# OpenMPPT2-Control.net
KiCad netlist of a schematic drawn in Altium Designer
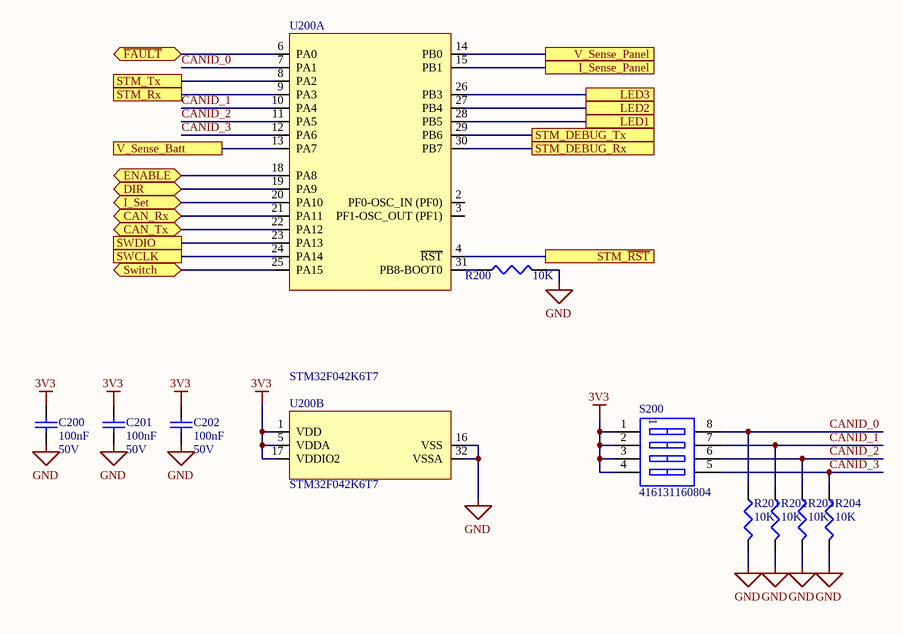
[diagram p0: OpenMPPT2-Control.SchDoc]

(export (version "E")
  (design (tool "Eeschema 10.0.6"))
  (components
    (comp (ref "C200")
      (value "100nF")
      (footprint "C0603")
      (description "Capacitor, 100nF, 50V, X7R")
      (fields (field (name "VOLTAGE RATING") "50V"))
      (libsource (lib "SBT_Capacitors_Ceramic") (part "100nF/0603/CER/50V"))
    )
    (comp (ref "C201")
      (value "100nF")
      (footprint "C0603")
      (description "Capacitor, 100nF, 50V, X7R")
      (fields (field (name "VOLTAGE RATING") "50V"))
      (libsource (lib "SBT_Capacitors_Ceramic") (part "100nF/0603/CER/50V"))
    )
    (comp (ref "C202")
      (value "100nF")
      (footprint "C0603")
      (description "Capacitor, 100nF, 50V, X7R")
      (fields (field (name "VOLTAGE RATING") "50V"))
      (libsource (lib "SBT_Capacitors_Ceramic") (part "100nF/0603/CER/50V"))
    )
    (comp (ref "R200")
      (value "10K")
      (footprint "0603")
      (description "Resistor, 10K, 1%, 0.063W, 50V, 100PPM, 0603")
      (libsource (lib "SBT_Resistors_SMD") (part "10K/0603/0063W/50V"))
    )
    (comp (ref "R201")
      (value "10K")
      (footprint "0603")
      (description "Resistor, 10K, 1%, 0.063W, 50V, 100PPM, 0603")
      (libsource (lib "SBT_Resistors_SMD") (part "10K/0603/0063W/50V"))
    )
    (comp (ref "R202")
      (value "10K")
      (footprint "0603")
      (description "Resistor, 10K, 1%, 0.063W, 50V, 100PPM, 0603")
      (libsource (lib "SBT_Resistors_SMD") (part "10K/0603/0063W/50V"))
    )
    (comp (ref "R203")
      (value "10K")
      (footprint "0603")
      (description "Resistor, 10K, 1%, 0.063W, 50V, 100PPM, 0603")
      (libsource (lib "SBT_Resistors_SMD") (part "10K/0603/0063W/50V"))
    )
    (comp (ref "R204")
      (value "10K")
      (footprint "0603")
      (description "Resistor, 10K, 1%, 0.063W, 50V, 100PPM, 0603")
      (libsource (lib "SBT_Resistors_SMD") (part "10K/0603/0063W/50V"))
    )
    (comp (ref "S200")
      (value "416131160804")
      (footprint "416131160804")
      (description "1.27 mm small compact SMD flat actuator with top tape WS-DISV")
      (fields (field (name "PUBLISHER") "Wurth Elektronik"))
      (libsource (lib "ALTIUM-WS-DISV-rev17b") (part "416131160804"))
    )
    (comp (ref "U200")
      (value "STM32F042K6T7")
      (footprint "LQFP32")
      (description "32 Bit Microcontroller, USB Line, ARM Cortex-M0, 48 MHz, 128 KB, 16 KB, 48, LQFP")
      (libsource (lib "SBT_Microcontrollers") (part "STM32F042K6T7"))
    )
  )
  (nets
    (net (code "1") (name "/CANID_0") (class "Default")
      (node (ref "R201") (pin "1") (pinfunction "1_1") (pintype "passive"))
      (node (ref "S200") (pin "8") (pinfunction "8_8") (pintype "passive"))
      (node (ref "U200") (pin "7") (pinfunction "PA1_7") (pintype "bidirectional"))
    )
    (net (code "2") (name "/CANID_1") (class "Default")
      (node (ref "R202") (pin "1") (pinfunction "1_1") (pintype "passive"))
      (node (ref "S200") (pin "7") (pinfunction "7_7") (pintype "passive"))
      (node (ref "U200") (pin "10") (pinfunction "PA4_10") (pintype "bidirectional"))
    )
    (net (code "3") (name "/CANID_2") (class "Default")
      (node (ref "R203") (pin "1") (pinfunction "1_1") (pintype "passive"))
      (node (ref "S200") (pin "6") (pinfunction "6_6") (pintype "passive"))
      (node (ref "U200") (pin "11") (pinfunction "PA5_11") (pintype "bidirectional"))
    )
    (net (code "4") (name "/CANID_3") (class "Default")
      (node (ref "R204") (pin "1") (pinfunction "1_1") (pintype "passive"))
      (node (ref "S200") (pin "5") (pinfunction "5_5") (pintype "passive"))
      (node (ref "U200") (pin "12") (pinfunction "PA6_12") (pintype "bidirectional"))
    )
    (net (code "5") (name "/CAN_Rx") (class "Default")
      (node (ref "U200") (pin "21") (pinfunction "PA11_21") (pintype "bidirectional"))
    )
    (net (code "6") (name "/CAN_Tx") (class "Default")
      (node (ref "U200") (pin "22") (pinfunction "PA12_22") (pintype "bidirectional"))
    )
    (net (code "7") (name "/DIR") (class "Default")
      (node (ref "U200") (pin "19") (pinfunction "PA9_19") (pintype "bidirectional"))
    )
    (net (code "8") (name "/ENABLE") (class "Default")
      (node (ref "U200") (pin "18") (pinfunction "PA8_18") (pintype "bidirectional"))
    )
    (net (code "9") (name "/I_Sense_Panel") (class "Default")
      (node (ref "U200") (pin "15") (pinfunction "PB1_15") (pintype "bidirectional"))
    )
    (net (code "10") (name "/I_Set") (class "Default")
      (node (ref "U200") (pin "20") (pinfunction "PA10_20") (pintype "bidirectional"))
    )
    (net (code "11") (name "/LED1") (class "Default")
      (node (ref "U200") (pin "28") (pinfunction "PB5_28") (pintype "bidirectional"))
    )
    (net (code "12") (name "/LED2") (class "Default")
      (node (ref "U200") (pin "27") (pinfunction "PB4_27") (pintype "bidirectional"))
    )
    (net (code "13") (name "/LED3") (class "Default")
      (node (ref "U200") (pin "26") (pinfunction "PB3_26") (pintype "bidirectional"))
    )
    (net (code "14") (name "/STM_DEBUG_Rx") (class "Default")
      (node (ref "U200") (pin "30") (pinfunction "PB7_30") (pintype "bidirectional"))
    )
    (net (code "15") (name "/STM_DEBUG_Tx") (class "Default")
      (node (ref "U200") (pin "29") (pinfunction "PB6_29") (pintype "bidirectional"))
    )
    (net (code "16") (name "/STM_Rx") (class "Default")
      (node (ref "U200") (pin "9") (pinfunction "PA3_9") (pintype "bidirectional"))
    )
    (net (code "17") (name "/STM_Tx") (class "Default")
      (node (ref "U200") (pin "8") (pinfunction "PA2_8") (pintype "bidirectional"))
    )
    (net (code "18") (name "/STM_~{RST}") (class "Default")
      (node (ref "U200") (pin "4") (pinfunction "~{RST}_4") (pintype "bidirectional"))
    )
    (net (code "19") (name "/SWCLK") (class "Default")
      (node (ref "U200") (pin "24") (pinfunction "PA14_24") (pintype "bidirectional"))
    )
    (net (code "20") (name "/SWDIO") (class "Default")
      (node (ref "U200") (pin "23") (pinfunction "PA13_23") (pintype "bidirectional"))
    )
    (net (code "21") (name "/Switch") (class "Default")
      (node (ref "U200") (pin "25") (pinfunction "PA15_25") (pintype "bidirectional"))
    )
    (net (code "22") (name "/V_Sense_Batt") (class "Default")
      (node (ref "U200") (pin "13") (pinfunction "PA7_13") (pintype "bidirectional"))
    )
    (net (code "23") (name "/V_Sense_Panel") (class "Default")
      (node (ref "U200") (pin "14") (pinfunction "PB0_14") (pintype "bidirectional"))
    )
    (net (code "24") (name "/~{FAULT}") (class "Default")
      (node (ref "U200") (pin "6") (pinfunction "PA0_6") (pintype "bidirectional"))
    )
    (net (code "25") (name "3V3") (class "Default")
      (node (ref "C200") (pin "2") (pinfunction "2_2") (pintype "passive"))
      (node (ref "C201") (pin "2") (pinfunction "2_2") (pintype "passive"))
      (node (ref "C202") (pin "2") (pinfunction "2_2") (pintype "passive"))
      (node (ref "S200") (pin "1") (pinfunction "1_1") (pintype "passive"))
      (node (ref "S200") (pin "2") (pinfunction "2_2") (pintype "passive"))
      (node (ref "S200") (pin "3") (pinfunction "3_3") (pintype "passive"))
      (node (ref "S200") (pin "4") (pinfunction "4_4") (pintype "passive"))
      (node (ref "U200") (pin "1") (pinfunction "VDD_1") (pintype "power_in"))
      (node (ref "U200") (pin "17") (pinfunction "VDDIO2_17") (pintype "power_in"))
      (node (ref "U200") (pin "5") (pinfunction "VDDA_5") (pintype "power_in"))
    )
    (net (code "26") (name "GND") (class "Default")
      (node (ref "C200") (pin "1") (pinfunction "1_1") (pintype "passive"))
      (node (ref "C201") (pin "1") (pinfunction "1_1") (pintype "passive"))
      (node (ref "C202") (pin "1") (pinfunction "1_1") (pintype "passive"))
      (node (ref "R200") (pin "2") (pinfunction "2_2") (pintype "passive"))
      (node (ref "R201") (pin "2") (pinfunction "2_2") (pintype "passive"))
      (node (ref "R202") (pin "2") (pinfunction "2_2") (pintype "passive"))
      (node (ref "R203") (pin "2") (pinfunction "2_2") (pintype "passive"))
      (node (ref "R204") (pin "2") (pinfunction "2_2") (pintype "passive"))
      (node (ref "U200") (pin "16") (pinfunction "VSS_16") (pintype "power_in"))
      (node (ref "U200") (pin "32") (pinfunction "VSSA_32") (pintype "power_in"))
    )
    (net (code "27") (name "Net-(U200A-PB8-BOOT0)") (class "Default")
      (node (ref "R200") (pin "1") (pinfunction "1_1") (pintype "passive"))
      (node (ref "U200") (pin "31") (pinfunction "PB8-BOOT0_31") (pintype "bidirectional"))
    )
    (net (code "28") (name "unconnected-(U200A-PF0-OSC_IN_(PF0)-Pad2)") (class "Default")
      (node (ref "U200") (pin "2") (pinfunction "PF0-OSC_IN_(PF0)_2") (pintype "bidirectional"))
    )
    (net (code "29") (name "unconnected-(U200A-PF1-OSC_OUT_(PF1)-Pad3)") (class "Default")
      (node (ref "U200") (pin "3") (pinfunction "PF1-OSC_OUT_(PF1)_3") (pintype "bidirectional"))
    )
  )
)
